# ProPrj_BSPD_2026-01-23.net
KiCad netlist of a schematic drawn in EasyEDA Pro
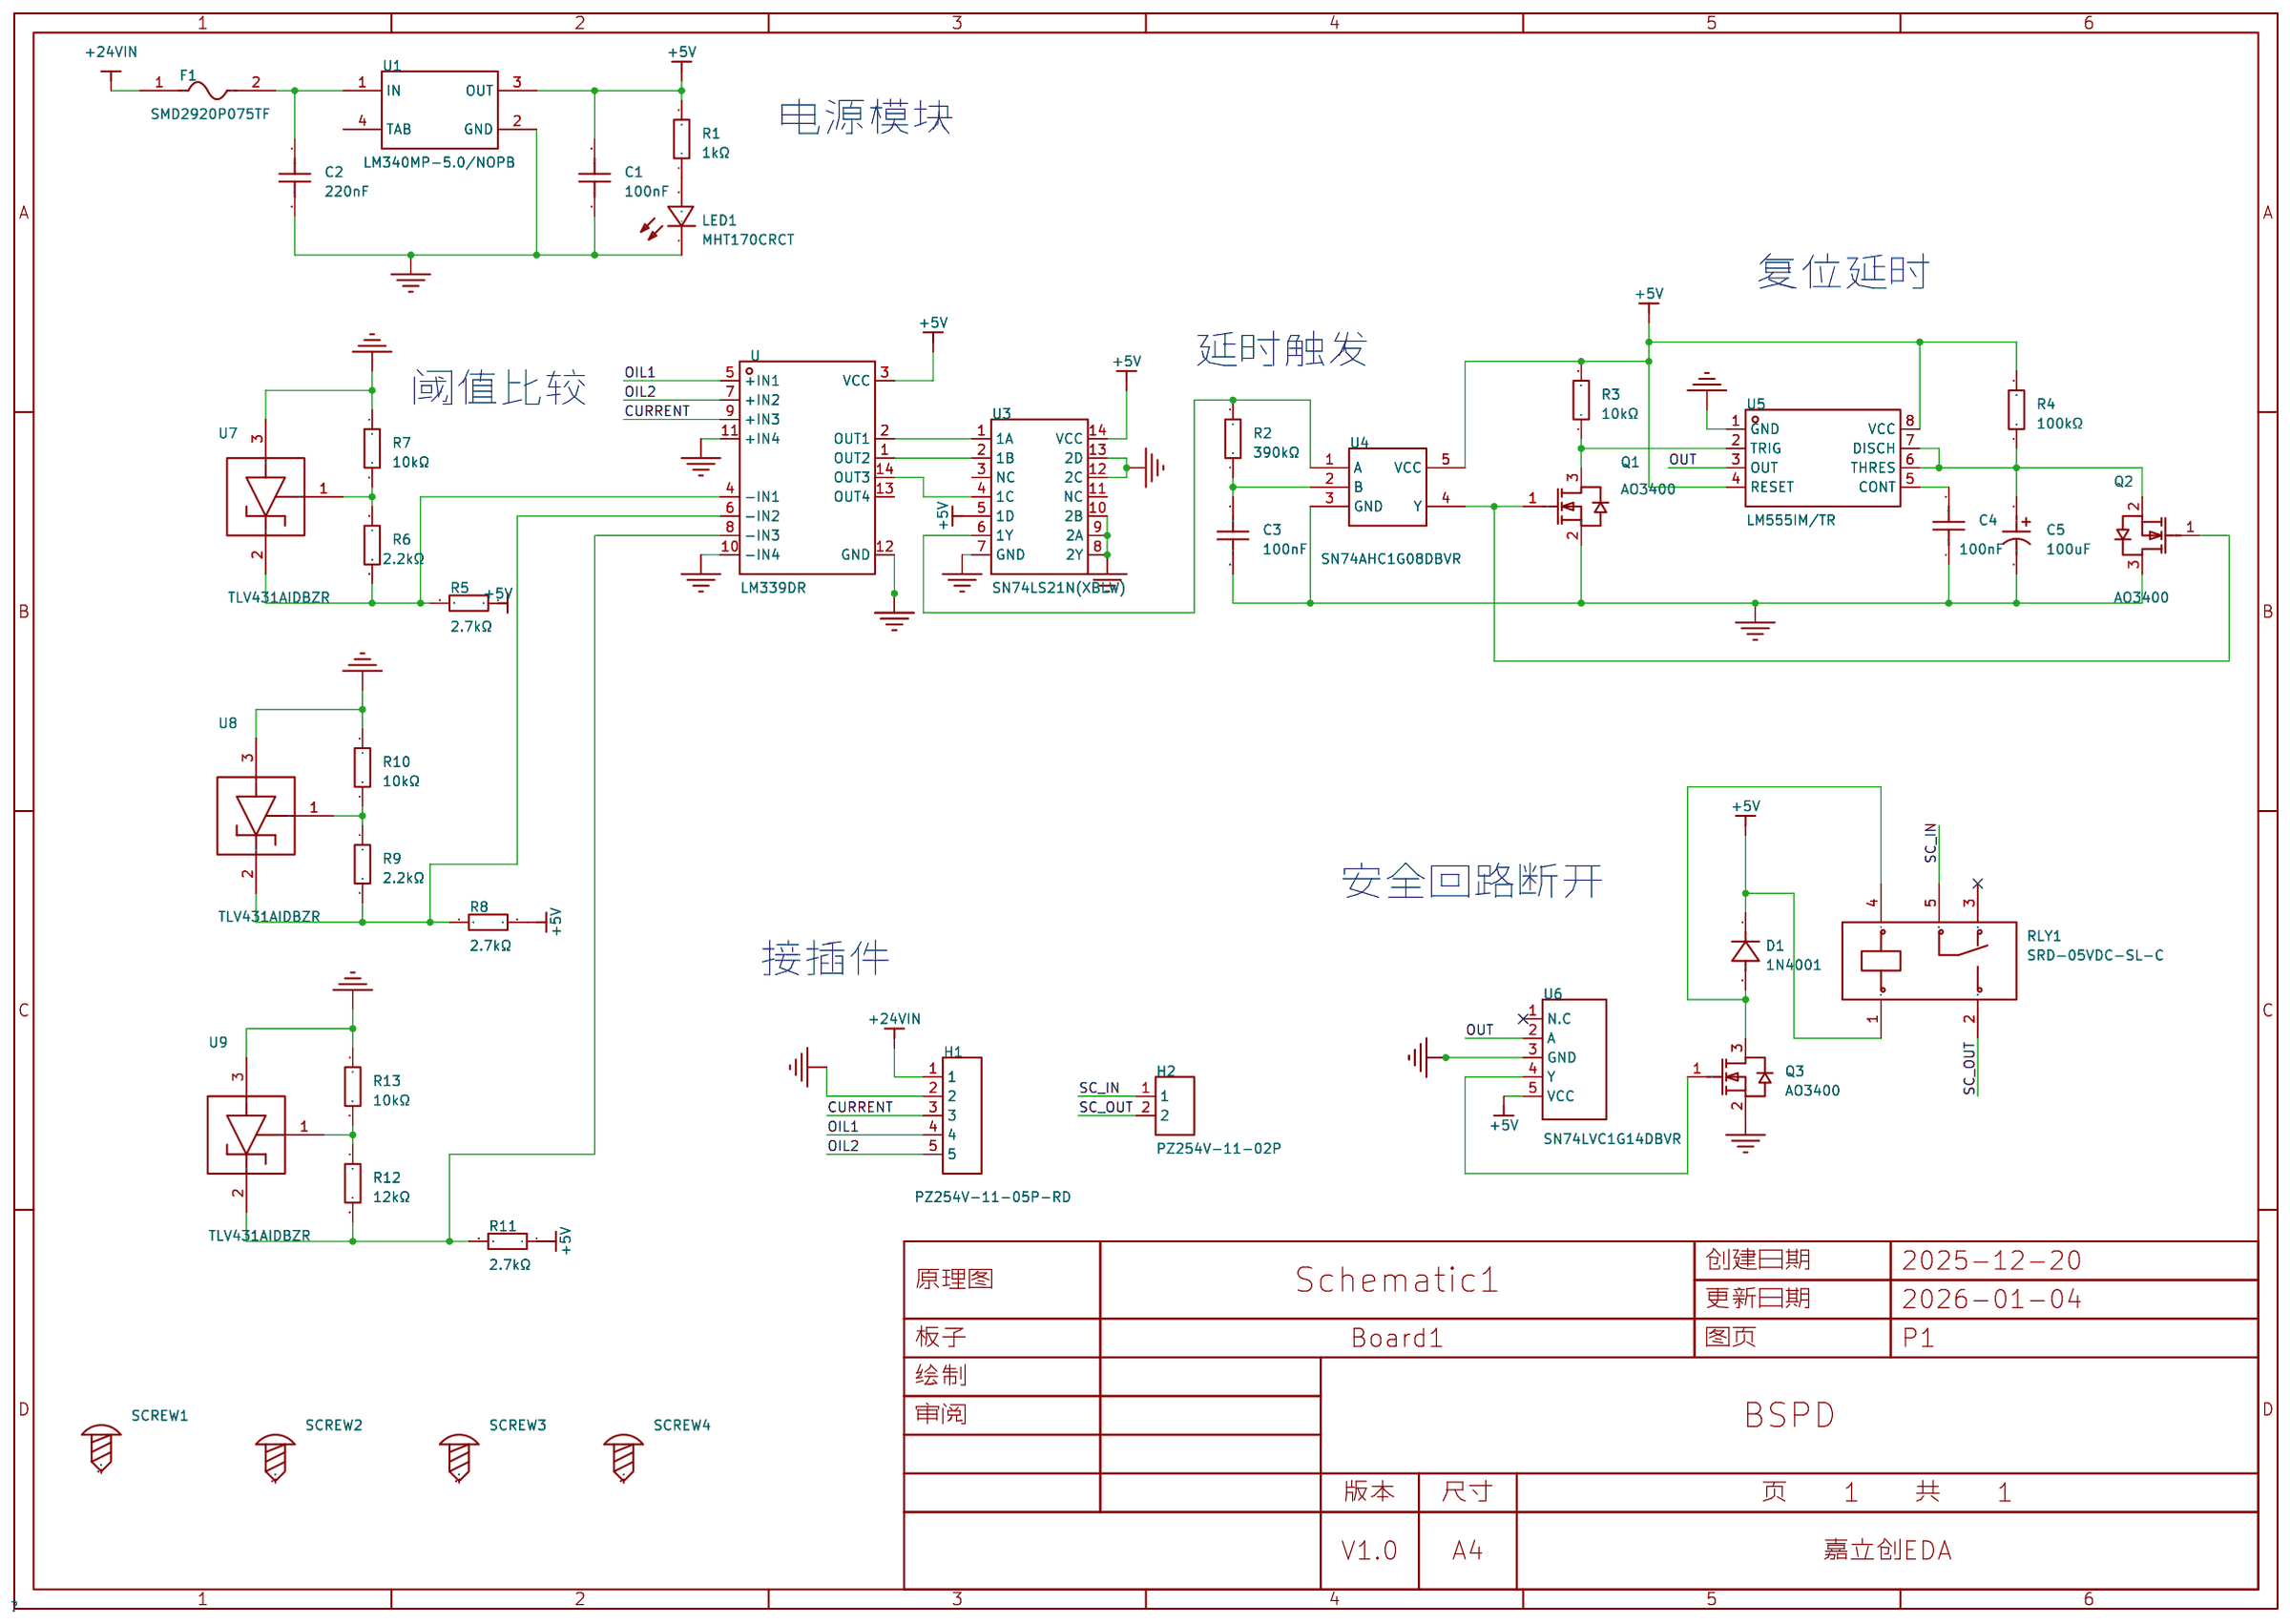
[diagram p0: schematic sheet]

(export (version "E")
  (design (tool "Eeschema 10.0.6"))
  (components
    (comp (ref "C1")
      (value "100nF")
      (footprint "easyedapro:C0603")
      (fields
        (field (name "Manufacturer Part") "CGA0603X7R104K500JT")
        (field (name "Manufacturer") "HRE(芯声)")
      )
      (libsource (lib "easyedapro") (part "CGA0603X7R104K500JT"))
    )
    (comp (ref "C2")
      (value "220nF")
      (footprint "easyedapro:C0603")
      (fields
        (field (name "Manufacturer Part") "CGA0603X7R104K500JT")
        (field (name "Manufacturer") "HRE(芯声)")
      )
      (libsource (lib "easyedapro") (part "CGA0603X7R104K500JT"))
    )
    (comp (ref "C3")
      (value "100nF")
      (footprint "easyedapro:C0603")
      (fields
        (field (name "Manufacturer Part") "CGA0603X7R104K500JT")
        (field (name "Manufacturer") "HRE(芯声)")
      )
      (libsource (lib "easyedapro") (part "CGA0603X7R104K500JT"))
    )
    (comp (ref "C4")
      (value "100nF")
      (footprint "easyedapro:C0603")
      (fields
        (field (name "Manufacturer Part") "CGA0603X7R104K500JT")
        (field (name "Manufacturer") "HRE(芯声)")
      )
      (libsource (lib "easyedapro") (part "CGA0603X7R104K500JT"))
    )
    (comp (ref "C5")
      (value "100uF")
      (footprint "easyedapro:CAP-SMD_BD6.3-L6.6-W6.6-FD-1")
      (fields (field (name "Manufacturer Part") "JVJ25V100M6x5") (field (name "Manufacturer") "JIERR(捷而瑞)"))
      (libsource (lib "easyedapro") (part "JVJ25V100M6X5"))
    )
    (comp (ref "D1")
      (value "1N4001")
      (footprint "easyedapro:SMA_L4.3-W2.5-LS5.0-RD")
      (fields (field (name "Manufacturer") "TWGMC(迪嘉)"))
      (libsource (lib "easyedapro") (part "1N4001_C727079"))
    )
    (comp (ref "F1")
      (value "SMD2920P075TF")
      (footprint "easyedapro:F2920")
      (fields (field (name "Manufacturer") "RUILON(瑞隆源)"))
      (libsource (lib "easyedapro") (part "SMD2920P075TF"))
    )
    (comp (ref "H1")
      (value "PZ254V-11-05P-RD")
      (footprint "easyedapro:HDR-TH_5P-P2.54-V-M")
      (fields (field (name "Manufacturer") "XFCN(兴飞)"))
      (libsource (lib "easyedapro") (part "PZ254V-11-05P-RD"))
    )
    (comp (ref "H2")
      (value "PZ254V-11-02P")
      (footprint "easyedapro:HDR-TH_2P-P2.54-V-M")
      (fields (field (name "Manufacturer") "XFCN(兴飞)"))
      (libsource (lib "easyedapro") (part "PZ254V-11-02P"))
    )
    (comp (ref "LED1")
      (value "MHT170CRCT")
      (footprint "easyedapro:LED0805-RD")
      (fields (field (name "Manufacturer") "MEIHUA(美华)"))
      (libsource (lib "easyedapro") (part "MHT170CRCT"))
    )
    (comp (ref "Q1")
      (value "AO3400")
      (footprint "easyedapro:SOT-23_L2.9-W1.3-P1.90-LS2.4-BR")
      (fields (field (name "Manufacturer") "GOODWORK(固得沃克)"))
      (libsource (lib "easyedapro") (part "AO3400_C2938367"))
    )
    (comp (ref "Q2")
      (value "AO3400")
      (footprint "easyedapro:SOT-23_L2.9-W1.3-P1.90-LS2.4-BR")
      (fields (field (name "Manufacturer") "GOODWORK(固得沃克)"))
      (libsource (lib "easyedapro") (part "AO3400_C2938367"))
    )
    (comp (ref "Q3")
      (value "AO3400")
      (footprint "easyedapro:SOT-23_L2.9-W1.3-P1.90-LS2.4-BR")
      (fields (field (name "Manufacturer") "GOODWORK(固得沃克)"))
      (libsource (lib "easyedapro") (part "AO3400_C2938367"))
    )
    (comp (ref "R1")
      (value "1kΩ")
      (footprint "easyedapro:R0603")
      (fields
        (field (name "Manufacturer Part") "0603WAF1002T5E")
        (field (name "Manufacturer") "UNI-ROYAL(厚声)")
      )
      (libsource (lib "easyedapro") (part "0603WAF1002T5E"))
    )
    (comp (ref "R2")
      (value "390kΩ")
      (footprint "easyedapro:R0603")
      (fields
        (field (name "Manufacturer Part") "0603WAF1002T5E")
        (field (name "Manufacturer") "UNI-ROYAL(厚声)")
      )
      (libsource (lib "easyedapro") (part "0603WAF1002T5E"))
    )
    (comp (ref "R3")
      (value "10kΩ")
      (footprint "easyedapro:R0603")
      (fields
        (field (name "Manufacturer Part") "0603WAF1002T5E")
        (field (name "Manufacturer") "UNI-ROYAL(厚声)")
      )
      (libsource (lib "easyedapro") (part "0603WAF1002T5E"))
    )
    (comp (ref "R4")
      (value "100kΩ")
      (footprint "easyedapro:R0603")
      (fields
        (field (name "Manufacturer Part") "0603WAF1003T5E")
        (field (name "Manufacturer") "UNI-ROYAL(厚声)")
      )
      (libsource (lib "easyedapro") (part "0603WAF1003T5E"))
    )
    (comp (ref "R5")
      (value "2.7kΩ")
      (footprint "easyedapro:R0603")
      (fields
        (field (name "Manufacturer Part") "0603WAF1002T5E")
        (field (name "Manufacturer") "UNI-ROYAL(厚声)")
      )
      (libsource (lib "easyedapro") (part "0603WAF1002T5E"))
    )
    (comp (ref "R6")
      (value "2.2kΩ")
      (footprint "easyedapro:R0603")
      (fields
        (field (name "Manufacturer Part") "0603WAF1002T5E")
        (field (name "Manufacturer") "UNI-ROYAL(厚声)")
      )
      (libsource (lib "easyedapro") (part "0603WAF1002T5E"))
    )
    (comp (ref "R7")
      (value "10kΩ")
      (footprint "easyedapro:R0603")
      (fields
        (field (name "Manufacturer Part") "0603WAF1002T5E")
        (field (name "Manufacturer") "UNI-ROYAL(厚声)")
      )
      (libsource (lib "easyedapro") (part "0603WAF1002T5E"))
    )
    (comp (ref "R8")
      (value "2.7kΩ")
      (footprint "easyedapro:R0603")
      (fields
        (field (name "Manufacturer Part") "0603WAF1002T5E")
        (field (name "Manufacturer") "UNI-ROYAL(厚声)")
      )
      (libsource (lib "easyedapro") (part "0603WAF1002T5E"))
    )
    (comp (ref "R9")
      (value "2.2kΩ")
      (footprint "easyedapro:R0603")
      (fields
        (field (name "Manufacturer Part") "0603WAF1002T5E")
        (field (name "Manufacturer") "UNI-ROYAL(厚声)")
      )
      (libsource (lib "easyedapro") (part "0603WAF1002T5E"))
    )
    (comp (ref "R10")
      (value "10kΩ")
      (footprint "easyedapro:R0603")
      (fields
        (field (name "Manufacturer Part") "0603WAF1002T5E")
        (field (name "Manufacturer") "UNI-ROYAL(厚声)")
      )
      (libsource (lib "easyedapro") (part "0603WAF1002T5E"))
    )
    (comp (ref "R11")
      (value "2.7kΩ")
      (footprint "easyedapro:R0603")
      (fields
        (field (name "Manufacturer Part") "0603WAF1002T5E")
        (field (name "Manufacturer") "UNI-ROYAL(厚声)")
      )
      (libsource (lib "easyedapro") (part "0603WAF1002T5E"))
    )
    (comp (ref "R12")
      (value "12kΩ")
      (footprint "easyedapro:R0603")
      (fields
        (field (name "Manufacturer Part") "0603WAF1002T5E")
        (field (name "Manufacturer") "UNI-ROYAL(厚声)")
      )
      (libsource (lib "easyedapro") (part "0603WAF1002T5E"))
    )
    (comp (ref "R13")
      (value "10kΩ")
      (footprint "easyedapro:R0603")
      (fields
        (field (name "Manufacturer Part") "0603WAF1002T5E")
        (field (name "Manufacturer") "UNI-ROYAL(厚声)")
      )
      (libsource (lib "easyedapro") (part "0603WAF1002T5E"))
    )
    (comp (ref "RLY1")
      (value "SRD-05VDC-SL-C")
      (footprint "easyedapro:RELAY-TH_SRD-XXVDC-XL-C")
      (fields (field (name "Manufacturer") "松乐"))
      (libsource (lib "easyedapro") (part "SRD-05VDC-SL-C"))
    )
    (comp (ref "SCREW1")
      (value "~")
      (footprint "easyedapro:M2螺丝")
      (libsource (lib "easyedapro") (part "螺丝孔"))
    )
    (comp (ref "SCREW2")
      (value "~")
      (footprint "easyedapro:M2螺丝")
      (libsource (lib "easyedapro") (part "螺丝孔"))
    )
    (comp (ref "SCREW3")
      (value "~")
      (footprint "easyedapro:M2螺丝")
      (libsource (lib "easyedapro") (part "螺丝孔"))
    )
    (comp (ref "SCREW4")
      (value "~")
      (footprint "easyedapro:M2螺丝")
      (libsource (lib "easyedapro") (part "螺丝孔"))
    )
    (comp (ref "U")
      (value "LM339DR")
      (footprint "easyedapro:SOIC-14_L8.7-W3.9-P1.27-LS6.0-BL")
      (fields (field (name "Manufacturer") "UMW(友台半导体)"))
      (libsource (lib "easyedapro") (part "LM339DR_C5236695"))
    )
    (comp (ref "U1")
      (value "LM340MP-5.0/NOPB")
      (footprint "easyedapro:SOT-223_L6.5-W3.5-P2.30-LS7.0-BR")
      (description "输出类型:固定;工作电压:35V;输出电压:5V;输出电流:1A;电源纹波抑制比(PSRR):70dB@(120Hz);输出极性:正极;")
      (fields (field (name "Manufacturer") "TI(德州仪器)"))
      (libsource (lib "easyedapro") (part "LM340MP-5.0/NOPB"))
    )
    (comp (ref "U3")
      (value "SN74LS21N(XBLW)")
      (footprint "easyedapro:DIP-14_L19.0-W6.4-P2.54-LS7.6-BL")
      (description "逻辑类型:与门;通道数:2;工作电压:2V~6V;静态电流(Iq):20uA;传播延迟(tpd):19ns@6.0V,50pF;")
      (fields (field (name "Manufacturer") "XBLW(芯伯乐)"))
      (libsource (lib "easyedapro") (part "SN74LS21N(XBLW)"))
    )
    (comp (ref "U4")
      (value "SN74AHC1G08DBVR")
      (footprint "easyedapro:SOT-23-5_L3.0-W1.7-P0.95-LS2.8-BR")
      (fields (field (name "Manufacturer") "TI(德州仪器)"))
      (libsource (lib "easyedapro") (part "SN74AHC1G08DBVRG4"))
    )
    (comp (ref "U5")
      (value "LM555IM/TR")
      (footprint "easyedapro:SOIC-8_L4.9-W3.9-P1.27-LS6.0-BL")
      (fields (field (name "Manufacturer") "HGSEMI(华冠)"))
      (libsource (lib "easyedapro") (part "LM555IM/TR"))
    )
    (comp (ref "U6")
      (value "SN74LVC1G14DBVR")
      (footprint "easyedapro:SOT-23-5_L3.0-W1.7-P0.95-LS2.8-BR")
      (fields (field (name "Manufacturer") "TI(德州仪器)"))
      (libsource (lib "easyedapro") (part "SN74LVC1G14DBVR"))
    )
    (comp (ref "U7")
      (value "TLV431AIDBZR")
      (footprint "easyedapro:SOT-23-3_L2.9-W1.3-P1.90-LS2.4-BR")
      (fields (field (name "Manufacturer") "TI(德州仪器)"))
      (libsource (lib "easyedapro") (part "TLV431AIDBZR"))
    )
    (comp (ref "U8")
      (value "TLV431AIDBZR")
      (footprint "easyedapro:SOT-23-3_L2.9-W1.3-P1.90-LS2.4-BR")
      (fields (field (name "Manufacturer") "TI(德州仪器)"))
      (libsource (lib "easyedapro") (part "TLV431AIDBZR"))
    )
    (comp (ref "U9")
      (value "TLV431AIDBZR")
      (footprint "easyedapro:SOT-23-3_L2.9-W1.3-P1.90-LS2.4-BR")
      (fields (field (name "Manufacturer") "TI(德州仪器)"))
      (libsource (lib "easyedapro") (part "TLV431AIDBZR"))
    )
  )
  (nets
    (net (code "1") (name "+5V") (class "Default")
      (node (ref "C1") (pin "2") (pinfunction "2_2") (pintype "unspecified"))
      (node (ref "D1") (pin "1") (pinfunction "K_1") (pintype "unspecified"))
      (node (ref "R1") (pin "2") (pinfunction "2_2") (pintype "input"))
      (node (ref "R11") (pin "1") (pinfunction "1_1") (pintype "input"))
      (node (ref "R3") (pin "2") (pinfunction "2_2") (pintype "input"))
      (node (ref "R4") (pin "2") (pinfunction "2_2") (pintype "input"))
      (node (ref "R5") (pin "1") (pinfunction "1_1") (pintype "input"))
      (node (ref "R8") (pin "1") (pinfunction "1_1") (pintype "input"))
      (node (ref "RLY1") (pin "1") (pinfunction "1_1") (pintype "input"))
      (node (ref "U") (pin "3") (pinfunction "VCC_3") (pintype "unspecified"))
      (node (ref "U1") (pin "3") (pinfunction "OUT_3") (pintype "unspecified"))
      (node (ref "U3") (pin "14") (pinfunction "VCC_14") (pintype "unspecified"))
      (node (ref "U3") (pin "5") (pinfunction "1D_5") (pintype "unspecified"))
      (node (ref "U4") (pin "5") (pinfunction "VCC_5") (pintype "unspecified"))
      (node (ref "U5") (pin "4") (pinfunction "RESET_4") (pintype "unspecified"))
      (node (ref "U5") (pin "8") (pinfunction "VCC_8") (pintype "unspecified"))
      (node (ref "U6") (pin "5") (pinfunction "VCC_5") (pintype "unspecified"))
    )
    (net (code "2") (name "+24VIN") (class "Default")
      (node (ref "F1") (pin "1") (pinfunction "1_1") (pintype "unspecified"))
      (node (ref "H1") (pin "1") (pinfunction "1_1") (pintype "unspecified"))
    )
    (net (code "3") (name "/CURRENT") (class "Default")
      (node (ref "H1") (pin "3") (pinfunction "3_3") (pintype "unspecified"))
      (node (ref "U") (pin "9") (pinfunction "+IN3_9") (pintype "unspecified"))
    )
    (net (code "4") (name "/OIL1") (class "Default")
      (node (ref "H1") (pin "4") (pinfunction "4_4") (pintype "unspecified"))
      (node (ref "U") (pin "5") (pinfunction "+IN1_5") (pintype "unspecified"))
    )
    (net (code "5") (name "/OIL2") (class "Default")
      (node (ref "H1") (pin "5") (pinfunction "5_5") (pintype "unspecified"))
      (node (ref "U") (pin "7") (pinfunction "+IN2_7") (pintype "unspecified"))
    )
    (net (code "6") (name "/OUT") (class "Default")
      (node (ref "U5") (pin "3") (pinfunction "OUT_3") (pintype "unspecified"))
      (node (ref "U6") (pin "2") (pinfunction "A_2") (pintype "unspecified"))
    )
    (net (code "7") (name "/SC_IN") (class "Default")
      (node (ref "H2") (pin "1") (pinfunction "1_1") (pintype "unspecified"))
      (node (ref "RLY1") (pin "5") (pinfunction "5_5") (pintype "input"))
    )
    (net (code "8") (name "/SC_OUT") (class "Default")
      (node (ref "H2") (pin "2") (pinfunction "2_2") (pintype "unspecified"))
      (node (ref "RLY1") (pin "2") (pinfunction "2_2") (pintype "input"))
    )
    (net (code "9") (name "GND") (class "Default")
      (node (ref "C1") (pin "1") (pinfunction "1_1") (pintype "unspecified"))
      (node (ref "C2") (pin "2") (pinfunction "2_2") (pintype "unspecified"))
      (node (ref "C3") (pin "2") (pinfunction "2_2") (pintype "unspecified"))
      (node (ref "C4") (pin "1") (pinfunction "1_1") (pintype "unspecified"))
      (node (ref "C5") (pin "2") (pinfunction "2_2") (pintype "input"))
      (node (ref "H1") (pin "2") (pinfunction "2_2") (pintype "unspecified"))
      (node (ref "LED1") (pin "1") (pinfunction "-_1") (pintype "unspecified"))
      (node (ref "Q1") (pin "2") (pinfunction "S_2") (pintype "unspecified"))
      (node (ref "Q2") (pin "3") (pinfunction "D_3") (pintype "unspecified"))
      (node (ref "Q3") (pin "2") (pinfunction "S_2") (pintype "unspecified"))
      (node (ref "R10") (pin "1") (pinfunction "1_1") (pintype "input"))
      (node (ref "R13") (pin "1") (pinfunction "1_1") (pintype "input"))
      (node (ref "R7") (pin "1") (pinfunction "1_1") (pintype "input"))
      (node (ref "U") (pin "10") (pinfunction "-IN4_10") (pintype "unspecified"))
      (node (ref "U") (pin "11") (pinfunction "+IN4_11") (pintype "unspecified"))
      (node (ref "U") (pin "12") (pinfunction "GND_12") (pintype "unspecified"))
      (node (ref "U1") (pin "2") (pinfunction "GND_2") (pintype "unspecified"))
      (node (ref "U3") (pin "10") (pinfunction "2B_10") (pintype "unspecified"))
      (node (ref "U3") (pin "12") (pinfunction "2C_12") (pintype "unspecified"))
      (node (ref "U3") (pin "13") (pinfunction "2D_13") (pintype "unspecified"))
      (node (ref "U3") (pin "7") (pinfunction "GND_7") (pintype "unspecified"))
      (node (ref "U3") (pin "8") (pinfunction "2Y_8") (pintype "unspecified"))
      (node (ref "U3") (pin "9") (pinfunction "2A_9") (pintype "unspecified"))
      (node (ref "U4") (pin "3") (pinfunction "GND_3") (pintype "unspecified"))
      (node (ref "U5") (pin "1") (pinfunction "GND_1") (pintype "unspecified"))
      (node (ref "U6") (pin "3") (pinfunction "GND_3") (pintype "unspecified"))
      (node (ref "U7") (pin "3") (pinfunction "A_3") (pintype "unspecified"))
      (node (ref "U8") (pin "3") (pinfunction "A_3") (pintype "unspecified"))
      (node (ref "U9") (pin "3") (pinfunction "A_3") (pintype "unspecified"))
    )
    (net (code "10") (name "Net-(D1-A)") (class "Default")
      (node (ref "D1") (pin "2") (pinfunction "A_2") (pintype "unspecified"))
      (node (ref "Q3") (pin "3") (pinfunction "D_3") (pintype "unspecified"))
      (node (ref "RLY1") (pin "4") (pinfunction "4_4") (pintype "input"))
    )
    (net (code "11") (name "Net-(LED1-+)") (class "Default")
      (node (ref "LED1") (pin "2") (pinfunction "+_2") (pintype "unspecified"))
      (node (ref "R1") (pin "1") (pinfunction "1_1") (pintype "input"))
    )
    (net (code "12") (name "Net-(Q1-D)") (class "Default")
      (node (ref "Q1") (pin "3") (pinfunction "D_3") (pintype "unspecified"))
      (node (ref "R3") (pin "1") (pinfunction "1_1") (pintype "input"))
      (node (ref "U5") (pin "2") (pinfunction "TRIG_2") (pintype "unspecified"))
    )
    (net (code "13") (name "Net-(Q1-G)") (class "Default")
      (node (ref "Q1") (pin "1") (pinfunction "G_1") (pintype "unspecified"))
      (node (ref "Q2") (pin "1") (pinfunction "G_1") (pintype "unspecified"))
      (node (ref "U4") (pin "4") (pinfunction "Y_4") (pintype "unspecified"))
    )
    (net (code "14") (name "Net-(Q2-S)") (class "Default")
      (node (ref "C5") (pin "1") (pinfunction "1_1") (pintype "input"))
      (node (ref "Q2") (pin "2") (pinfunction "S_2") (pintype "unspecified"))
      (node (ref "R4") (pin "1") (pinfunction "1_1") (pintype "input"))
      (node (ref "U5") (pin "6") (pinfunction "THRES_6") (pintype "unspecified"))
      (node (ref "U5") (pin "7") (pinfunction "DISCH_7") (pintype "unspecified"))
    )
    (net (code "15") (name "Net-(Q3-G)") (class "Default")
      (node (ref "Q3") (pin "1") (pinfunction "G_1") (pintype "unspecified"))
      (node (ref "U6") (pin "4") (pinfunction "Y_4") (pintype "unspecified"))
    )
    (net (code "16") (name "Net-(U--IN1)") (class "Default")
      (node (ref "R5") (pin "2") (pinfunction "2_2") (pintype "input"))
      (node (ref "R6") (pin "2") (pinfunction "2_2") (pintype "input"))
      (node (ref "U") (pin "4") (pinfunction "-IN1_4") (pintype "unspecified"))
      (node (ref "U7") (pin "2") (pinfunction "C_2") (pintype "unspecified"))
    )
    (net (code "17") (name "Net-(U--IN2)") (class "Default")
      (node (ref "R8") (pin "2") (pinfunction "2_2") (pintype "input"))
      (node (ref "R9") (pin "2") (pinfunction "2_2") (pintype "input"))
      (node (ref "U") (pin "6") (pinfunction "-IN2_6") (pintype "unspecified"))
      (node (ref "U8") (pin "2") (pinfunction "C_2") (pintype "unspecified"))
    )
    (net (code "18") (name "Net-(U--IN3)") (class "Default")
      (node (ref "R11") (pin "2") (pinfunction "2_2") (pintype "input"))
      (node (ref "R12") (pin "2") (pinfunction "2_2") (pintype "input"))
      (node (ref "U") (pin "8") (pinfunction "-IN3_8") (pintype "unspecified"))
      (node (ref "U9") (pin "2") (pinfunction "C_2") (pintype "unspecified"))
    )
    (net (code "19") (name "Net-(U-OUT1)") (class "Default")
      (node (ref "U") (pin "2") (pinfunction "OUT1_2") (pintype "unspecified"))
      (node (ref "U3") (pin "1") (pinfunction "1A_1") (pintype "unspecified"))
    )
    (net (code "20") (name "Net-(U-OUT2)") (class "Default")
      (node (ref "U") (pin "1") (pinfunction "OUT2_1") (pintype "unspecified"))
      (node (ref "U3") (pin "2") (pinfunction "1B_2") (pintype "unspecified"))
    )
    (net (code "21") (name "Net-(U-OUT3)") (class "Default")
      (node (ref "U") (pin "14") (pinfunction "OUT3_14") (pintype "unspecified"))
      (node (ref "U3") (pin "4") (pinfunction "1C_4") (pintype "unspecified"))
    )
    (net (code "22") (name "Net-(U1-IN)") (class "Default")
      (node (ref "C2") (pin "1") (pinfunction "1_1") (pintype "unspecified"))
      (node (ref "F1") (pin "2") (pinfunction "2_2") (pintype "unspecified"))
      (node (ref "U1") (pin "1") (pinfunction "IN_1") (pintype "unspecified"))
    )
    (net (code "23") (name "Net-(U3-1Y)") (class "Default")
      (node (ref "R2") (pin "2") (pinfunction "2_2") (pintype "input"))
      (node (ref "U3") (pin "6") (pinfunction "1Y_6") (pintype "unspecified"))
      (node (ref "U4") (pin "1") (pinfunction "A_1") (pintype "unspecified"))
    )
    (net (code "24") (name "Net-(U4-B)") (class "Default")
      (node (ref "C3") (pin "1") (pinfunction "1_1") (pintype "unspecified"))
      (node (ref "R2") (pin "1") (pinfunction "1_1") (pintype "input"))
      (node (ref "U4") (pin "2") (pinfunction "B_2") (pintype "unspecified"))
    )
    (net (code "25") (name "Net-(U5-CONT)") (class "Default")
      (node (ref "C4") (pin "2") (pinfunction "2_2") (pintype "unspecified"))
      (node (ref "U5") (pin "5") (pinfunction "CONT_5") (pintype "unspecified"))
    )
    (net (code "26") (name "Net-(U7-REF)") (class "Default")
      (node (ref "R6") (pin "1") (pinfunction "1_1") (pintype "input"))
      (node (ref "R7") (pin "2") (pinfunction "2_2") (pintype "input"))
      (node (ref "U7") (pin "1") (pinfunction "REF_1") (pintype "unspecified"))
    )
    (net (code "27") (name "Net-(U8-REF)") (class "Default")
      (node (ref "R10") (pin "2") (pinfunction "2_2") (pintype "input"))
      (node (ref "R9") (pin "1") (pinfunction "1_1") (pintype "input"))
      (node (ref "U8") (pin "1") (pinfunction "REF_1") (pintype "unspecified"))
    )
    (net (code "28") (name "Net-(U9-REF)") (class "Default")
      (node (ref "R12") (pin "1") (pinfunction "1_1") (pintype "input"))
      (node (ref "R13") (pin "2") (pinfunction "2_2") (pintype "input"))
      (node (ref "U9") (pin "1") (pinfunction "REF_1") (pintype "unspecified"))
    )
    (net (code "29") (name "unconnected-(RLY1-Pad3)") (class "Default")
      (node (ref "RLY1") (pin "3") (pinfunction "3_3") (pintype "input+no_connect"))
    )
    (net (code "30") (name "unconnected-(SCREW1-Pad1)") (class "Default")
      (node (ref "SCREW1") (pin "1") (pinfunction "1_1") (pintype "input"))
    )
    (net (code "31") (name "unconnected-(SCREW2-Pad1)") (class "Default")
      (node (ref "SCREW2") (pin "1") (pinfunction "1_1") (pintype "input"))
    )
    (net (code "32") (name "unconnected-(SCREW3-Pad1)") (class "Default")
      (node (ref "SCREW3") (pin "1") (pinfunction "1_1") (pintype "input"))
    )
    (net (code "33") (name "unconnected-(SCREW4-Pad1)") (class "Default")
      (node (ref "SCREW4") (pin "1") (pinfunction "1_1") (pintype "input"))
    )
    (net (code "34") (name "unconnected-(U-OUT4-Pad13)") (class "Default")
      (node (ref "U") (pin "13") (pinfunction "OUT4_13") (pintype "unspecified"))
    )
    (net (code "35") (name "unconnected-(U1-TAB-Pad4)") (class "Default")
      (node (ref "U1") (pin "4") (pinfunction "TAB_4") (pintype "unspecified"))
    )
    (net (code "36") (name "unconnected-(U3-NC-Pad3)") (class "Default")
      (node (ref "U3") (pin "3") (pinfunction "NC_3") (pintype "unspecified"))
    )
    (net (code "37") (name "unconnected-(U3-NC-Pad11)") (class "Default")
      (node (ref "U3") (pin "11") (pinfunction "NC_11") (pintype "unspecified"))
    )
    (net (code "38") (name "unconnected-(U6-N.C-Pad1)") (class "Default")
      (node (ref "U6") (pin "1") (pinfunction "N.C_1") (pintype "unspecified+no_connect"))
    )
  )
)
